# tps63020-buck-boost-flashlight-driver-17.net
KiCad netlist of a schematic drawn in EAGLE
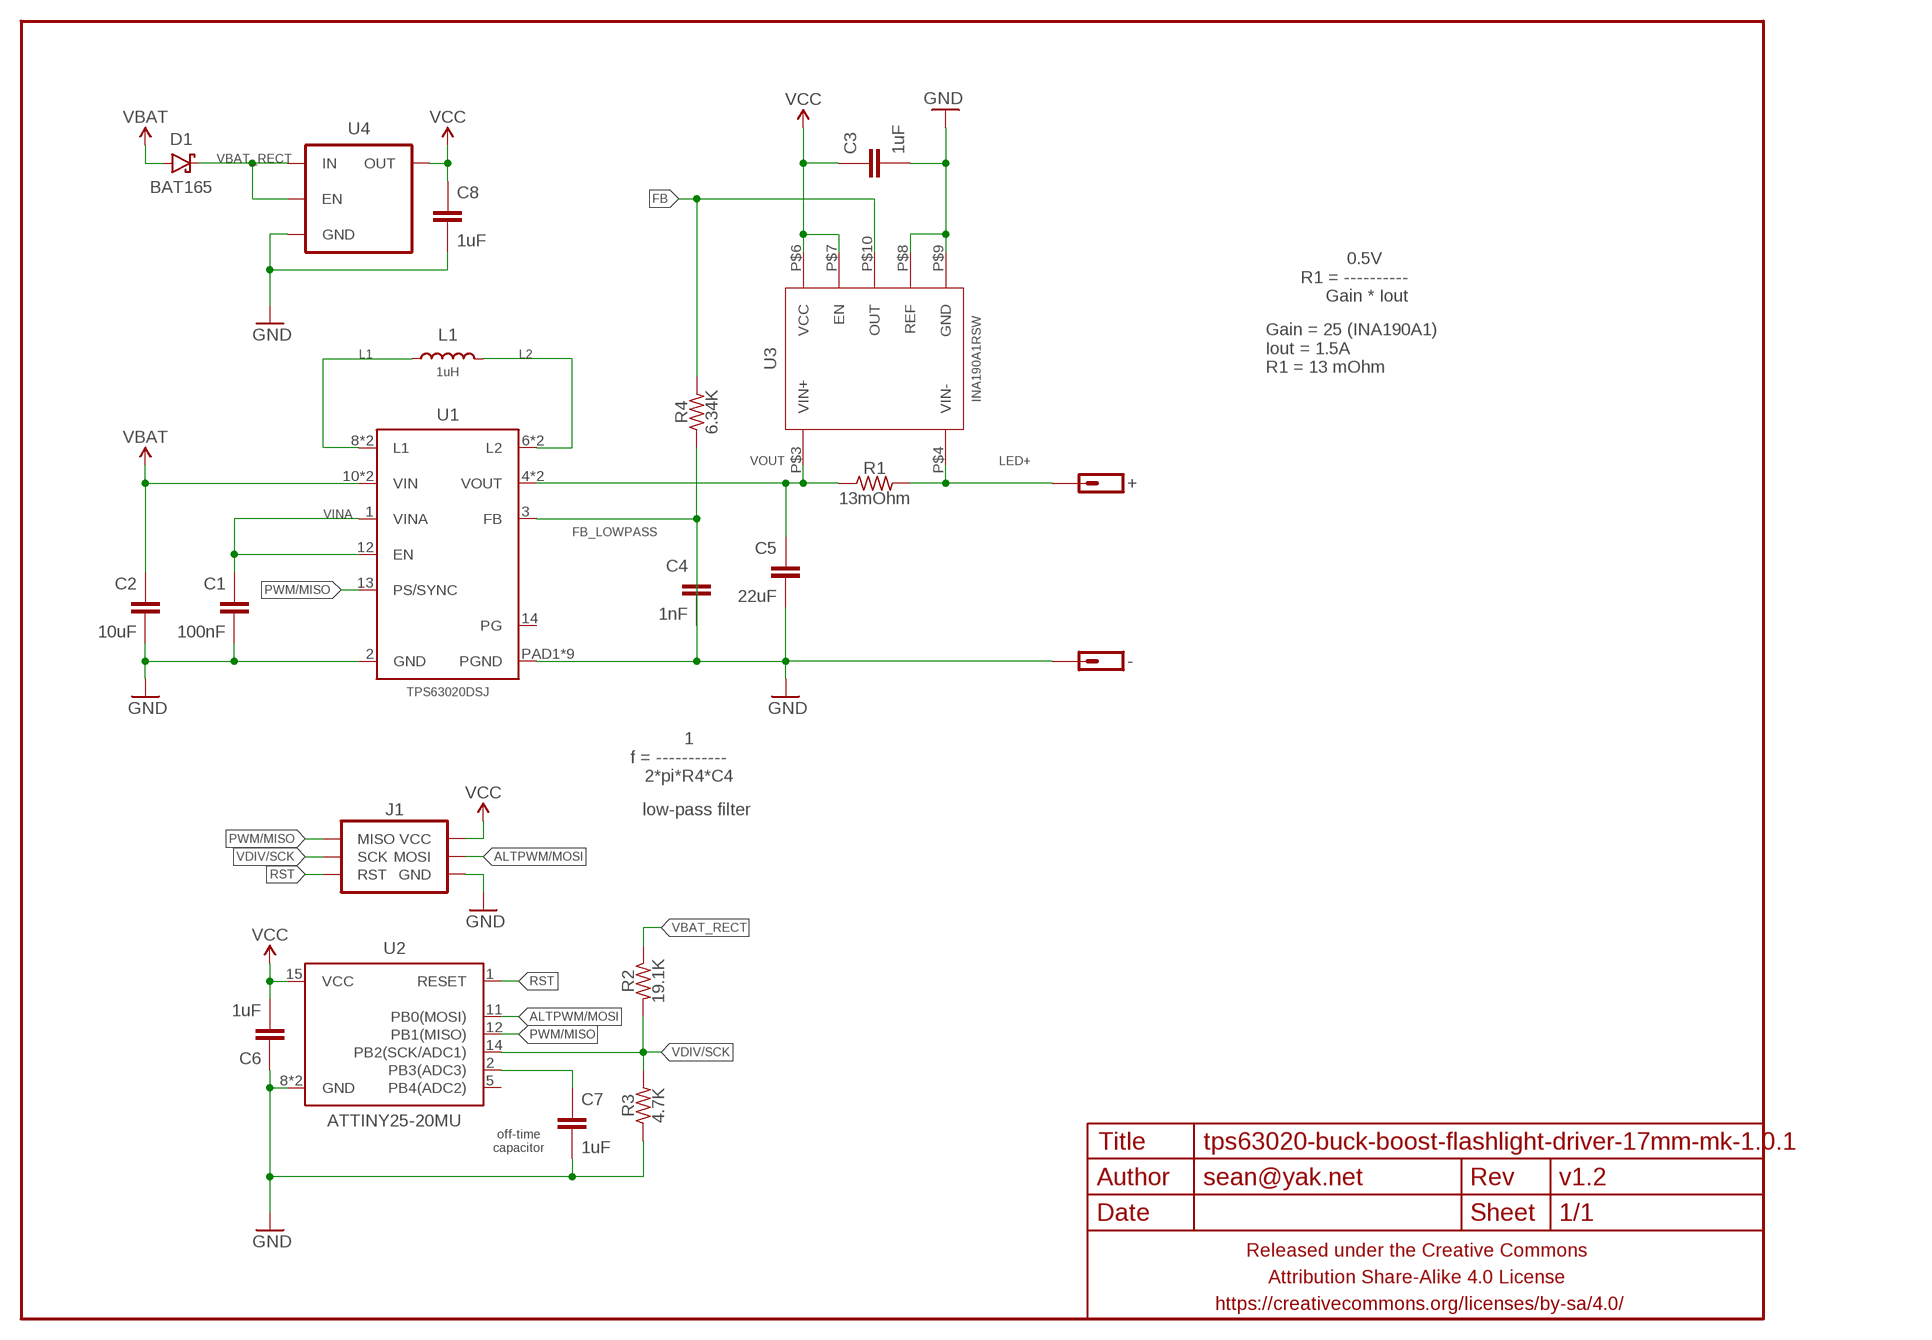
[diagram p0: schematic, sheet 1]

(export (version "E")
  (design (tool "Eeschema 10.0.6"))
  (components
    (comp (ref "+")
      (value "M01PTH-1MM-CIR-NS")
      (footprint "eagle-import:1X01-1MM-CIR-NS")
      (libsource (lib "eagle-import") (part "M01PTH-1MM-CIR-NS"))
    )
    (comp (ref "-")
      (value "M01PTH-1MM-CIR-NS")
      (footprint "eagle-import:1X01-1MM-CIR-NS")
      (libsource (lib "eagle-import") (part "M01PTH-1MM-CIR-NS"))
    )
    (comp (ref "C1")
      (value "100nF")
      (footprint "eagle-import:C0402")
      (libsource (lib "eagle-import") (part "CAPACITOR-CERAMICC0402"))
    )
    (comp (ref "C2")
      (value "10uF")
      (footprint "eagle-import:C0805-TIGHTER")
      (libsource (lib "eagle-import") (part "CAPACITOR-CERAMICC0805-TIGHTER"))
    )
    (comp (ref "C3")
      (value "1uF")
      (footprint "eagle-import:C0402")
      (libsource (lib "eagle-import") (part "CAPACITOR-CERAMICC0402"))
    )
    (comp (ref "C4")
      (value "1nF")
      (footprint "eagle-import:C0402")
      (libsource (lib "eagle-import") (part "CAPACITOR-CERAMICC0402"))
    )
    (comp (ref "C5")
      (value "22uF")
      (footprint "eagle-import:C0805-TIGHTER")
      (libsource (lib "eagle-import") (part "CAPACITOR-CERAMICC0805-TIGHTER"))
    )
    (comp (ref "C6")
      (value "1uF")
      (footprint "eagle-import:C0402")
      (libsource (lib "eagle-import") (part "CAPACITOR-CERAMICC0402"))
    )
    (comp (ref "C7")
      (value "1uF")
      (footprint "eagle-import:C0402")
      (libsource (lib "eagle-import") (part "CAPACITOR-CERAMICC0402"))
    )
    (comp (ref "C8")
      (value "1uF")
      (footprint "eagle-import:C0402")
      (libsource (lib "eagle-import") (part "CAPACITOR-CERAMICC0402"))
    )
    (comp (ref "D1")
      (value "BAT165")
      (footprint "eagle-import:SOD323-SCHOTTKY")
      (libsource (lib "eagle-import") (part "DIODE-SCHOTTKYSOD323"))
    )
    (comp (ref "FRAME1")
      (value "FRAME-LETTERNO_PACKAGE")
      (footprint "eagle-import:DUMMY")
      (fields
        (field (name "DESIGNER") "Nobody")
        (field (name "VERSION") "v01")
        (field (name "DESIGNER_1") "sean@yak.net")
        (field (name "VERSION_1") "v1.2")
      )
      (libsource (lib "eagle-import") (part "FRAME-LETTERNO_PACKAGE"))
    )
    (comp (ref "J1")
      (value "AVR_SPI_PRG_6SMD-1.27MM")
      (footprint "eagle-import:2X3-1.27MM-SMD")
      (libsource (lib "eagle-import") (part "AVR_SPI_PRG_6SMD-1.27MM"))
    )
    (comp (ref "L1")
      (value "1uH")
      (footprint "eagle-import:XAL50X0")
      (libsource (lib "eagle-import") (part "INDUCTORXAL50X0"))
    )
    (comp (ref "R1")
      (value "13mOhm")
      (footprint "eagle-import:R0805-TIGHTER")
      (libsource (lib "eagle-import") (part "RESISTORR0805-TIGHTER"))
    )
    (comp (ref "R2")
      (value "19.1K")
      (footprint "eagle-import:R0402")
      (libsource (lib "eagle-import") (part "RESISTORR0402"))
    )
    (comp (ref "R3")
      (value "4.7K")
      (footprint "eagle-import:R0402")
      (libsource (lib "eagle-import") (part "RESISTORR0402"))
    )
    (comp (ref "R4")
      (value "6.34K")
      (footprint "eagle-import:R0402")
      (libsource (lib "eagle-import") (part "RESISTORR0402"))
    )
    (comp (ref "U1")
      (value "TPS63020DSJ")
      (footprint "eagle-import:VSON-14-4MMX3MM")
      (libsource (lib "eagle-import") (part "TPS63020DSJ"))
    )
    (comp (ref "U2")
      (value "ATTINY25-20MU")
      (footprint "eagle-import:QFN20")
      (libsource (lib "eagle-import") (part "ATTINY45TINY85-20-QFN"))
    )
    (comp (ref "U3")
      (value "INA190A1RSW")
      (footprint "eagle-import:UQFN-10")
      (libsource (lib "eagle-import") (part "INA190RSW"))
    )
    (comp (ref "U4")
      (value "V_REG_ENTLV700")
      (footprint "eagle-import:SC70")
      (libsource (lib "eagle-import") (part "V_REG_ENTLV700"))
    )
  )
  (nets
    (net (code "1") (name "/FB_LOWPASS") (class "Default")
      (node (ref "C4") (pin "2") (pinfunction "2_2") (pintype "passive"))
      (node (ref "R4") (pin "1") (pinfunction "1_1") (pintype "passive"))
      (node (ref "U1") (pin "3") (pinfunction "FB_3") (pintype "bidirectional"))
    )
    (net (code "2") (name "/L1") (class "Default")
      (node (ref "L1") (pin "P$1") (pinfunction "1_P$1") (pintype "passive"))
      (node (ref "U1") (pin "8") (pinfunction "L1_8") (pintype "bidirectional"))
      (node (ref "U1") (pin "9") (pinfunction "L1_9") (pintype "bidirectional"))
    )
    (net (code "3") (name "/L2") (class "Default")
      (node (ref "L1") (pin "P$2") (pinfunction "2_P$2") (pintype "passive"))
      (node (ref "U1") (pin "6") (pinfunction "L2_6") (pintype "bidirectional"))
      (node (ref "U1") (pin "7") (pinfunction "L2_7") (pintype "bidirectional"))
    )
    (net (code "4") (name "/LED+") (class "Default")
      (node (ref "+") (pin "1") (pinfunction "1_1") (pintype "passive"))
      (node (ref "R1") (pin "2") (pinfunction "2_2") (pintype "passive"))
      (node (ref "U3") (pin "P$4") (pinfunction "VIN-_P$4") (pintype "bidirectional"))
    )
    (net (code "5") (name "/VINA") (class "Default")
      (node (ref "C1") (pin "1") (pinfunction "1_1") (pintype "passive"))
      (node (ref "U1") (pin "1") (pinfunction "VINA_1") (pintype "bidirectional"))
      (node (ref "U1") (pin "12") (pinfunction "EN_12") (pintype "bidirectional"))
    )
    (net (code "6") (name "/VOUT") (class "Default")
      (node (ref "C5") (pin "1") (pinfunction "1_1") (pintype "passive"))
      (node (ref "R1") (pin "1") (pinfunction "1_1") (pintype "passive"))
      (node (ref "U1") (pin "4") (pinfunction "VOUT_4") (pintype "bidirectional"))
      (node (ref "U1") (pin "5") (pinfunction "VOUT_5") (pintype "bidirectional"))
      (node (ref "U3") (pin "P$3") (pinfunction "VIN+_P$3") (pintype "bidirectional"))
    )
    (net (code "7") (name "ALTPWM{slash}MOSI") (class "Default")
      (node (ref "J1") (pin "4") (pinfunction "MOSI_4") (pintype "passive"))
      (node (ref "U2") (pin "11") (pinfunction "PB0(MOSI)_11") (pintype "bidirectional"))
    )
    (net (code "8") (name "FB") (class "Default")
      (node (ref "R4") (pin "2") (pinfunction "2_2") (pintype "passive"))
      (node (ref "U3") (pin "P$10") (pinfunction "OUT_P$10") (pintype "bidirectional"))
    )
    (net (code "9") (name "GND") (class "Default")
      (node (ref "-") (pin "1") (pinfunction "1_1") (pintype "passive"))
      (node (ref "C1") (pin "2") (pinfunction "2_2") (pintype "passive"))
      (node (ref "C2") (pin "2") (pinfunction "2_2") (pintype "passive"))
      (node (ref "C3") (pin "2") (pinfunction "2_2") (pintype "passive"))
      (node (ref "C4") (pin "1") (pinfunction "1_1") (pintype "passive"))
      (node (ref "C5") (pin "2") (pinfunction "2_2") (pintype "passive"))
      (node (ref "C6") (pin "1") (pinfunction "1_1") (pintype "passive"))
      (node (ref "C7") (pin "2") (pinfunction "2_2") (pintype "passive"))
      (node (ref "C8") (pin "2") (pinfunction "2_2") (pintype "passive"))
      (node (ref "J1") (pin "6") (pinfunction "GND_6") (pintype "passive"))
      (node (ref "R3") (pin "1") (pinfunction "1_1") (pintype "passive"))
      (node (ref "U1") (pin "2") (pinfunction "GND_2") (pintype "bidirectional"))
      (node (ref "U1") (pin "PAD1") (pinfunction "PGND_PAD1") (pintype "bidirectional"))
      (node (ref "U1") (pin "PAD2") (pinfunction "PGND_PAD2") (pintype "bidirectional"))
      (node (ref "U1") (pin "PAD3") (pinfunction "PGND_PAD3") (pintype "bidirectional"))
      (node (ref "U1") (pin "PAD4") (pinfunction "PGND_PAD4") (pintype "bidirectional"))
      (node (ref "U1") (pin "PAD5") (pinfunction "PGND_PAD5") (pintype "bidirectional"))
      (node (ref "U1") (pin "PAD6") (pinfunction "PGND_PAD6") (pintype "bidirectional"))
      (node (ref "U1") (pin "PAD7") (pinfunction "PGND_PAD7") (pintype "bidirectional"))
      (node (ref "U1") (pin "PAD8") (pinfunction "PGND_PAD8") (pintype "bidirectional"))
      (node (ref "U1") (pin "PADCENTER") (pinfunction "PGND_PADCENTER") (pintype "bidirectional"))
      (node (ref "U2") (pin "8") (pinfunction "GND_8") (pintype "bidirectional"))
      (node (ref "U2") (pin "PAD") (pinfunction "GND_PAD") (pintype "bidirectional"))
      (node (ref "U3") (pin "P$8") (pinfunction "REF_P$8") (pintype "bidirectional"))
      (node (ref "U3") (pin "P$9") (pinfunction "GND_P$9") (pintype "bidirectional"))
      (node (ref "U4") (pin "2") (pinfunction "GND_2") (pintype "input"))
    )
    (net (code "10") (name "Net-(U2-PB3(ADC3))") (class "Default")
      (node (ref "C7") (pin "1") (pinfunction "1_1") (pintype "passive"))
      (node (ref "U2") (pin "2") (pinfunction "PB3(ADC3)_2") (pintype "bidirectional"))
    )
    (net (code "11") (name "PWM{slash}MISO") (class "Default")
      (node (ref "J1") (pin "1") (pinfunction "MISO_1") (pintype "passive"))
      (node (ref "U1") (pin "13") (pinfunction "PS/SYNC_13") (pintype "bidirectional"))
      (node (ref "U2") (pin "12") (pinfunction "PB1(MISO)_12") (pintype "bidirectional"))
    )
    (net (code "12") (name "RST") (class "Default")
      (node (ref "J1") (pin "5") (pinfunction "RST_5") (pintype "passive"))
      (node (ref "U2") (pin "1") (pinfunction "RESET_1") (pintype "bidirectional"))
    )
    (net (code "13") (name "VBAT") (class "Default")
      (node (ref "C2") (pin "1") (pinfunction "1_1") (pintype "passive"))
      (node (ref "D1") (pin "A") (pinfunction "A_A") (pintype "passive"))
      (node (ref "U1") (pin "10") (pinfunction "VIN_10") (pintype "bidirectional"))
      (node (ref "U1") (pin "11") (pinfunction "VIN_11") (pintype "bidirectional"))
    )
    (net (code "14") (name "VBAT_RECT") (class "Default")
      (node (ref "D1") (pin "C") (pinfunction "C_C") (pintype "passive"))
      (node (ref "R2") (pin "1") (pinfunction "1_1") (pintype "passive"))
      (node (ref "U4") (pin "1") (pinfunction "IN_1") (pintype "input"))
      (node (ref "U4") (pin "3") (pinfunction "EN_3") (pintype "input"))
    )
    (net (code "15") (name "VCC") (class "Default")
      (node (ref "C3") (pin "1") (pinfunction "1_1") (pintype "passive"))
      (node (ref "C6") (pin "2") (pinfunction "2_2") (pintype "passive"))
      (node (ref "C8") (pin "1") (pinfunction "1_1") (pintype "passive"))
      (node (ref "J1") (pin "2") (pinfunction "VCC_2") (pintype "passive"))
      (node (ref "U2") (pin "15") (pinfunction "VCC_15") (pintype "bidirectional"))
      (node (ref "U3") (pin "P$6") (pinfunction "VCC_P$6") (pintype "bidirectional"))
      (node (ref "U3") (pin "P$7") (pinfunction "EN_P$7") (pintype "bidirectional"))
      (node (ref "U4") (pin "5") (pinfunction "OUT_5") (pintype "passive"))
    )
    (net (code "16") (name "VDIV{slash}SCK") (class "Default")
      (node (ref "J1") (pin "3") (pinfunction "SCK_3") (pintype "passive"))
      (node (ref "R2") (pin "2") (pinfunction "2_2") (pintype "passive"))
      (node (ref "R3") (pin "2") (pinfunction "2_2") (pintype "passive"))
      (node (ref "U2") (pin "14") (pinfunction "PB2(SCK/ADC1)_14") (pintype "bidirectional"))
    )
    (net (code "17") (name "unconnected-(U1-PG-Pad14)") (class "Default")
      (node (ref "U1") (pin "14") (pinfunction "PG_14") (pintype "bidirectional"))
    )
    (net (code "18") (name "unconnected-(U2-PB4(ADC2)-Pad5)") (class "Default")
      (node (ref "U2") (pin "5") (pinfunction "PB4(ADC2)_5") (pintype "bidirectional"))
    )
  )
)
